# REDLED.net
KiCad netlist of a schematic drawn in Altium Designer
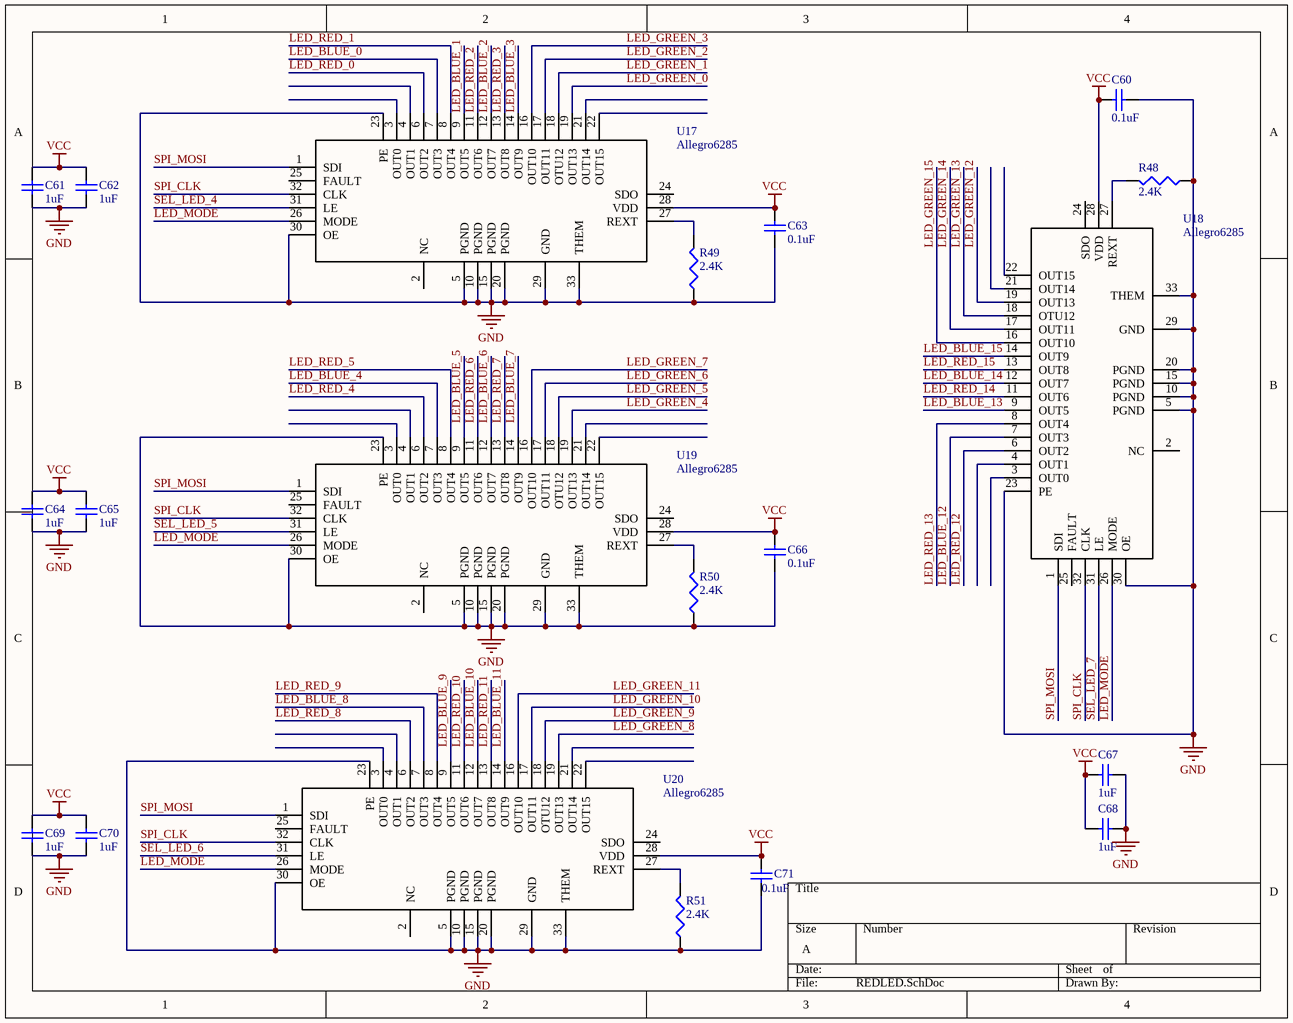
[diagram p0: REDLED.SchDoc]

(export (version "E")
  (design (tool "Eeschema 10.0.6"))
  (components
    (comp (ref "C60")
      (value "0.1uF")
      (footprint "CAPC1005L")
      (description "Capacitor (Semiconductor SIM Model)")
      (fields (field (name "Comment") "Cap Semi") (field (name "PUBLISHER") "Altium Limited"))
      (libsource (lib "Miscellaneous Devices") (part "Cap Semi"))
    )
    (comp (ref "C61")
      (value "1uF")
      (footprint "CAPC1608L")
      (description "Capacitor (Semiconductor SIM Model)")
      (fields (field (name "Comment") "Cap Semi") (field (name "PUBLISHER") "Altium Limited"))
      (libsource (lib "Miscellaneous Devices") (part "Cap Semi"))
    )
    (comp (ref "C62")
      (value "1uF")
      (footprint "CAPC1608L")
      (description "Capacitor (Semiconductor SIM Model)")
      (fields (field (name "Comment") "Cap Semi") (field (name "PUBLISHER") "Altium Limited"))
      (libsource (lib "Miscellaneous Devices") (part "Cap Semi"))
    )
    (comp (ref "C63")
      (value "0.1uF")
      (footprint "CAPC1005L")
      (description "Capacitor (Semiconductor SIM Model)")
      (fields (field (name "Comment") "Cap Semi") (field (name "PUBLISHER") "Altium Limited"))
      (libsource (lib "Miscellaneous Devices") (part "Cap Semi"))
    )
    (comp (ref "C64")
      (value "1uF")
      (footprint "CAPC1608L")
      (description "Capacitor (Semiconductor SIM Model)")
      (fields (field (name "Comment") "Cap Semi") (field (name "PUBLISHER") "Altium Limited"))
      (libsource (lib "Miscellaneous Devices") (part "Cap Semi"))
    )
    (comp (ref "C65")
      (value "1uF")
      (footprint "CAPC1608L")
      (description "Capacitor (Semiconductor SIM Model)")
      (fields (field (name "Comment") "Cap Semi") (field (name "PUBLISHER") "Altium Limited"))
      (libsource (lib "Miscellaneous Devices") (part "Cap Semi"))
    )
    (comp (ref "C66")
      (value "0.1uF")
      (footprint "CAPC1005L")
      (description "Capacitor (Semiconductor SIM Model)")
      (fields (field (name "Comment") "Cap Semi") (field (name "PUBLISHER") "Altium Limited"))
      (libsource (lib "Miscellaneous Devices") (part "Cap Semi"))
    )
    (comp (ref "C67")
      (value "1uF")
      (footprint "CAPC1608L")
      (description "Capacitor (Semiconductor SIM Model)")
      (fields (field (name "Comment") "Cap Semi") (field (name "PUBLISHER") "Altium Limited"))
      (libsource (lib "Miscellaneous Devices") (part "Cap Semi"))
    )
    (comp (ref "C68")
      (value "1uF")
      (footprint "CAPC1608L")
      (description "Capacitor (Semiconductor SIM Model)")
      (fields (field (name "Comment") "Cap Semi") (field (name "PUBLISHER") "Altium Limited"))
      (libsource (lib "Miscellaneous Devices") (part "Cap Semi"))
    )
    (comp (ref "C69")
      (value "1uF")
      (footprint "CAPC1608L")
      (description "Capacitor (Semiconductor SIM Model)")
      (fields (field (name "Comment") "Cap Semi") (field (name "PUBLISHER") "Altium Limited"))
      (libsource (lib "Miscellaneous Devices") (part "Cap Semi"))
    )
    (comp (ref "C70")
      (value "1uF")
      (footprint "CAPC1608L")
      (description "Capacitor (Semiconductor SIM Model)")
      (fields (field (name "Comment") "Cap Semi") (field (name "PUBLISHER") "Altium Limited"))
      (libsource (lib "Miscellaneous Devices") (part "Cap Semi"))
    )
    (comp (ref "C71")
      (value "0.1uF")
      (footprint "CAPC1005L")
      (description "Capacitor (Semiconductor SIM Model)")
      (fields (field (name "Comment") "Cap Semi") (field (name "PUBLISHER") "Altium Limited"))
      (libsource (lib "Miscellaneous Devices") (part "Cap Semi"))
    )
    (comp (ref "R48")
      (value "2.4K")
      (footprint "RESC1608L")
      (description "Resistor")
      (fields (field (name "Comment") "Res3") (field (name "PUBLISHER") "Altium Limited"))
      (libsource (lib "Miscellaneous Devices") (part "Res3"))
    )
    (comp (ref "R49")
      (value "2.4K")
      (footprint "RESC1608L")
      (description "Resistor")
      (fields (field (name "Comment") "Res3") (field (name "PUBLISHER") "Altium Limited"))
      (libsource (lib "Miscellaneous Devices") (part "Res3"))
    )
    (comp (ref "R50")
      (value "2.4K")
      (footprint "RESC1608L")
      (description "Resistor")
      (fields (field (name "Comment") "Res3") (field (name "PUBLISHER") "Altium Limited"))
      (libsource (lib "Miscellaneous Devices") (part "Res3"))
    )
    (comp (ref "R51")
      (value "2.4K")
      (footprint "RESC1608L")
      (description "Resistor")
      (fields (field (name "Comment") "Res3") (field (name "PUBLISHER") "Altium Limited"))
      (libsource (lib "Miscellaneous Devices") (part "Res3"))
    )
    (comp (ref "U17")
      (value "Allegro6285")
      (footprint "QFN-32")
      (libsource (lib "mrone") (part "Allegro6285"))
    )
    (comp (ref "U18")
      (value "Allegro6285")
      (footprint "QFN-32")
      (libsource (lib "mrone") (part "Allegro6285"))
    )
    (comp (ref "U19")
      (value "Allegro6285")
      (footprint "QFN-32")
      (libsource (lib "mrone") (part "Allegro6285"))
    )
    (comp (ref "U20")
      (value "Allegro6285")
      (footprint "QFN-32")
      (libsource (lib "mrone") (part "Allegro6285"))
    )
  )
  (nets
    (net (code "1") (name "/LED_BLUE_0") (class "Default")
      (node (ref "U17") (pin "7") (pinfunction "OUT3_7") (pintype "passive"))
    )
    (net (code "2") (name "/LED_BLUE_1") (class "Default")
      (node (ref "U17") (pin "9") (pinfunction "OUT5_9") (pintype "passive"))
    )
    (net (code "3") (name "/LED_BLUE_2") (class "Default")
      (node (ref "U17") (pin "12") (pinfunction "OUT7_12") (pintype "passive"))
    )
    (net (code "4") (name "/LED_BLUE_3") (class "Default")
      (node (ref "U17") (pin "14") (pinfunction "OUT9_14") (pintype "passive"))
    )
    (net (code "5") (name "/LED_BLUE_4") (class "Default")
      (node (ref "U19") (pin "7") (pinfunction "OUT3_7") (pintype "passive"))
    )
    (net (code "6") (name "/LED_BLUE_5") (class "Default")
      (node (ref "U19") (pin "9") (pinfunction "OUT5_9") (pintype "passive"))
    )
    (net (code "7") (name "/LED_BLUE_6") (class "Default")
      (node (ref "U19") (pin "12") (pinfunction "OUT7_12") (pintype "passive"))
    )
    (net (code "8") (name "/LED_BLUE_7") (class "Default")
      (node (ref "U19") (pin "14") (pinfunction "OUT9_14") (pintype "passive"))
    )
    (net (code "9") (name "/LED_BLUE_8") (class "Default")
      (node (ref "U20") (pin "7") (pinfunction "OUT3_7") (pintype "passive"))
    )
    (net (code "10") (name "/LED_BLUE_9") (class "Default")
      (node (ref "U20") (pin "9") (pinfunction "OUT5_9") (pintype "passive"))
    )
    (net (code "11") (name "/LED_BLUE_10") (class "Default")
      (node (ref "U20") (pin "12") (pinfunction "OUT7_12") (pintype "passive"))
    )
    (net (code "12") (name "/LED_BLUE_11") (class "Default")
      (node (ref "U20") (pin "14") (pinfunction "OUT9_14") (pintype "passive"))
    )
    (net (code "13") (name "/LED_BLUE_12") (class "Default")
      (node (ref "U18") (pin "7") (pinfunction "OUT3_7") (pintype "passive"))
    )
    (net (code "14") (name "/LED_BLUE_13") (class "Default")
      (node (ref "U18") (pin "9") (pinfunction "OUT5_9") (pintype "passive"))
    )
    (net (code "15") (name "/LED_BLUE_14") (class "Default")
      (node (ref "U18") (pin "12") (pinfunction "OUT7_12") (pintype "passive"))
    )
    (net (code "16") (name "/LED_BLUE_15") (class "Default")
      (node (ref "U18") (pin "14") (pinfunction "OUT9_14") (pintype "passive"))
    )
    (net (code "17") (name "/LED_GREEN_0") (class "Default")
      (node (ref "U17") (pin "19") (pinfunction "OUT13_19") (pintype "passive"))
    )
    (net (code "18") (name "/LED_GREEN_1") (class "Default")
      (node (ref "U17") (pin "18") (pinfunction "OTU12_18") (pintype "passive"))
    )
    (net (code "19") (name "/LED_GREEN_2") (class "Default")
      (node (ref "U17") (pin "17") (pinfunction "OUT11_17") (pintype "passive"))
    )
    (net (code "20") (name "/LED_GREEN_3") (class "Default")
      (node (ref "U17") (pin "16") (pinfunction "OUT10_16") (pintype "passive"))
    )
    (net (code "21") (name "/LED_GREEN_4") (class "Default")
      (node (ref "U19") (pin "19") (pinfunction "OUT13_19") (pintype "passive"))
    )
    (net (code "22") (name "/LED_GREEN_5") (class "Default")
      (node (ref "U19") (pin "18") (pinfunction "OTU12_18") (pintype "passive"))
    )
    (net (code "23") (name "/LED_GREEN_6") (class "Default")
      (node (ref "U19") (pin "17") (pinfunction "OUT11_17") (pintype "passive"))
    )
    (net (code "24") (name "/LED_GREEN_7") (class "Default")
      (node (ref "U19") (pin "16") (pinfunction "OUT10_16") (pintype "passive"))
    )
    (net (code "25") (name "/LED_GREEN_8") (class "Default")
      (node (ref "U20") (pin "19") (pinfunction "OUT13_19") (pintype "passive"))
    )
    (net (code "26") (name "/LED_GREEN_9") (class "Default")
      (node (ref "U20") (pin "18") (pinfunction "OTU12_18") (pintype "passive"))
    )
    (net (code "27") (name "/LED_GREEN_10") (class "Default")
      (node (ref "U20") (pin "17") (pinfunction "OUT11_17") (pintype "passive"))
    )
    (net (code "28") (name "/LED_GREEN_11") (class "Default")
      (node (ref "U20") (pin "16") (pinfunction "OUT10_16") (pintype "passive"))
    )
    (net (code "29") (name "/LED_GREEN_12") (class "Default")
      (node (ref "U18") (pin "19") (pinfunction "OUT13_19") (pintype "passive"))
    )
    (net (code "30") (name "/LED_GREEN_13") (class "Default")
      (node (ref "U18") (pin "18") (pinfunction "OTU12_18") (pintype "passive"))
    )
    (net (code "31") (name "/LED_GREEN_14") (class "Default")
      (node (ref "U18") (pin "17") (pinfunction "OUT11_17") (pintype "passive"))
    )
    (net (code "32") (name "/LED_GREEN_15") (class "Default")
      (node (ref "U18") (pin "16") (pinfunction "OUT10_16") (pintype "passive"))
    )
    (net (code "33") (name "/LED_MODE") (class "Default")
      (node (ref "U17") (pin "26") (pinfunction "MODE_26") (pintype "passive"))
      (node (ref "U18") (pin "26") (pinfunction "MODE_26") (pintype "passive"))
      (node (ref "U19") (pin "26") (pinfunction "MODE_26") (pintype "passive"))
      (node (ref "U20") (pin "26") (pinfunction "MODE_26") (pintype "passive"))
    )
    (net (code "34") (name "/LED_RED_0") (class "Default")
      (node (ref "U17") (pin "6") (pinfunction "OUT2_6") (pintype "passive"))
    )
    (net (code "35") (name "/LED_RED_1") (class "Default")
      (node (ref "U17") (pin "8") (pinfunction "OUT4_8") (pintype "passive"))
    )
    (net (code "36") (name "/LED_RED_2") (class "Default")
      (node (ref "U17") (pin "11") (pinfunction "OUT6_11") (pintype "passive"))
    )
    (net (code "37") (name "/LED_RED_3") (class "Default")
      (node (ref "U17") (pin "13") (pinfunction "OUT8_13") (pintype "passive"))
    )
    (net (code "38") (name "/LED_RED_4") (class "Default")
      (node (ref "U19") (pin "6") (pinfunction "OUT2_6") (pintype "passive"))
    )
    (net (code "39") (name "/LED_RED_5") (class "Default")
      (node (ref "U19") (pin "8") (pinfunction "OUT4_8") (pintype "passive"))
    )
    (net (code "40") (name "/LED_RED_6") (class "Default")
      (node (ref "U19") (pin "11") (pinfunction "OUT6_11") (pintype "passive"))
    )
    (net (code "41") (name "/LED_RED_7") (class "Default")
      (node (ref "U19") (pin "13") (pinfunction "OUT8_13") (pintype "passive"))
    )
    (net (code "42") (name "/LED_RED_8") (class "Default")
      (node (ref "U20") (pin "6") (pinfunction "OUT2_6") (pintype "passive"))
    )
    (net (code "43") (name "/LED_RED_9") (class "Default")
      (node (ref "U20") (pin "8") (pinfunction "OUT4_8") (pintype "passive"))
    )
    (net (code "44") (name "/LED_RED_10") (class "Default")
      (node (ref "U20") (pin "11") (pinfunction "OUT6_11") (pintype "passive"))
    )
    (net (code "45") (name "/LED_RED_11") (class "Default")
      (node (ref "U20") (pin "13") (pinfunction "OUT8_13") (pintype "passive"))
    )
    (net (code "46") (name "/LED_RED_12") (class "Default")
      (node (ref "U18") (pin "6") (pinfunction "OUT2_6") (pintype "passive"))
    )
    (net (code "47") (name "/LED_RED_13") (class "Default")
      (node (ref "U18") (pin "8") (pinfunction "OUT4_8") (pintype "passive"))
    )
    (net (code "48") (name "/LED_RED_14") (class "Default")
      (node (ref "U18") (pin "11") (pinfunction "OUT6_11") (pintype "passive"))
    )
    (net (code "49") (name "/LED_RED_15") (class "Default")
      (node (ref "U18") (pin "13") (pinfunction "OUT8_13") (pintype "passive"))
    )
    (net (code "50") (name "/SEL_LED_4") (class "Default")
      (node (ref "U17") (pin "31") (pinfunction "LE_31") (pintype "passive"))
    )
    (net (code "51") (name "/SEL_LED_5") (class "Default")
      (node (ref "U19") (pin "31") (pinfunction "LE_31") (pintype "passive"))
    )
    (net (code "52") (name "/SEL_LED_6") (class "Default")
      (node (ref "U20") (pin "31") (pinfunction "LE_31") (pintype "passive"))
    )
    (net (code "53") (name "/SEL_LED_7") (class "Default")
      (node (ref "U18") (pin "31") (pinfunction "LE_31") (pintype "passive"))
    )
    (net (code "54") (name "/SPI_CLK") (class "Default")
      (node (ref "U17") (pin "32") (pinfunction "CLK_32") (pintype "passive"))
      (node (ref "U18") (pin "32") (pinfunction "CLK_32") (pintype "passive"))
      (node (ref "U19") (pin "32") (pinfunction "CLK_32") (pintype "passive"))
      (node (ref "U20") (pin "32") (pinfunction "CLK_32") (pintype "passive"))
    )
    (net (code "55") (name "/SPI_MOSI") (class "Default")
      (node (ref "U17") (pin "1") (pinfunction "SDI_1") (pintype "passive"))
      (node (ref "U18") (pin "1") (pinfunction "SDI_1") (pintype "passive"))
      (node (ref "U19") (pin "1") (pinfunction "SDI_1") (pintype "passive"))
      (node (ref "U20") (pin "1") (pinfunction "SDI_1") (pintype "passive"))
    )
    (net (code "56") (name "GND") (class "Default")
      (node (ref "C60") (pin "1") (pinfunction "1_1") (pintype "passive"))
      (node (ref "C61") (pin "1") (pinfunction "1_1") (pintype "passive"))
      (node (ref "C62") (pin "1") (pinfunction "1_1") (pintype "passive"))
      (node (ref "C63") (pin "1") (pinfunction "1_1") (pintype "passive"))
      (node (ref "C64") (pin "1") (pinfunction "1_1") (pintype "passive"))
      (node (ref "C65") (pin "1") (pinfunction "1_1") (pintype "passive"))
      (node (ref "C66") (pin "1") (pinfunction "1_1") (pintype "passive"))
      (node (ref "C67") (pin "1") (pinfunction "1_1") (pintype "passive"))
      (node (ref "C68") (pin "1") (pinfunction "1_1") (pintype "passive"))
      (node (ref "C69") (pin "1") (pinfunction "1_1") (pintype "passive"))
      (node (ref "C70") (pin "1") (pinfunction "1_1") (pintype "passive"))
      (node (ref "C71") (pin "1") (pinfunction "1_1") (pintype "passive"))
      (node (ref "R48") (pin "1") (pinfunction "1_1") (pintype "passive"))
      (node (ref "R49") (pin "1") (pinfunction "1_1") (pintype "passive"))
      (node (ref "R50") (pin "1") (pinfunction "1_1") (pintype "passive"))
      (node (ref "R51") (pin "1") (pinfunction "1_1") (pintype "passive"))
      (node (ref "U17") (pin "10") (pinfunction "PGND_10") (pintype "passive"))
      (node (ref "U17") (pin "15") (pinfunction "PGND_15") (pintype "passive"))
      (node (ref "U17") (pin "20") (pinfunction "PGND_20") (pintype "passive"))
      (node (ref "U17") (pin "23") (pinfunction "PE_23") (pintype "passive"))
      (node (ref "U17") (pin "29") (pinfunction "GND_29") (pintype "passive"))
      (node (ref "U17") (pin "30") (pinfunction "OE_30") (pintype "passive"))
      (node (ref "U17") (pin "33") (pinfunction "THEM_33") (pintype "passive"))
      (node (ref "U17") (pin "5") (pinfunction "PGND_5") (pintype "passive"))
      (node (ref "U18") (pin "10") (pinfunction "PGND_10") (pintype "passive"))
      (node (ref "U18") (pin "15") (pinfunction "PGND_15") (pintype "passive"))
      (node (ref "U18") (pin "20") (pinfunction "PGND_20") (pintype "passive"))
      (node (ref "U18") (pin "23") (pinfunction "PE_23") (pintype "passive"))
      (node (ref "U18") (pin "29") (pinfunction "GND_29") (pintype "passive"))
      (node (ref "U18") (pin "30") (pinfunction "OE_30") (pintype "passive"))
      (node (ref "U18") (pin "33") (pinfunction "THEM_33") (pintype "passive"))
      (node (ref "U18") (pin "5") (pinfunction "PGND_5") (pintype "passive"))
      (node (ref "U19") (pin "10") (pinfunction "PGND_10") (pintype "passive"))
      (node (ref "U19") (pin "15") (pinfunction "PGND_15") (pintype "passive"))
      (node (ref "U19") (pin "20") (pinfunction "PGND_20") (pintype "passive"))
      (node (ref "U19") (pin "23") (pinfunction "PE_23") (pintype "passive"))
      (node (ref "U19") (pin "29") (pinfunction "GND_29") (pintype "passive"))
      (node (ref "U19") (pin "30") (pinfunction "OE_30") (pintype "passive"))
      (node (ref "U19") (pin "33") (pinfunction "THEM_33") (pintype "passive"))
      (node (ref "U19") (pin "5") (pinfunction "PGND_5") (pintype "passive"))
      (node (ref "U20") (pin "10") (pinfunction "PGND_10") (pintype "passive"))
      (node (ref "U20") (pin "15") (pinfunction "PGND_15") (pintype "passive"))
      (node (ref "U20") (pin "20") (pinfunction "PGND_20") (pintype "passive"))
      (node (ref "U20") (pin "23") (pinfunction "PE_23") (pintype "passive"))
      (node (ref "U20") (pin "29") (pinfunction "GND_29") (pintype "passive"))
      (node (ref "U20") (pin "30") (pinfunction "OE_30") (pintype "passive"))
      (node (ref "U20") (pin "33") (pinfunction "THEM_33") (pintype "passive"))
      (node (ref "U20") (pin "5") (pinfunction "PGND_5") (pintype "passive"))
    )
    (net (code "57") (name "Net-(U17-REXT)") (class "Default")
      (node (ref "R49") (pin "2") (pinfunction "2_2") (pintype "passive"))
      (node (ref "U17") (pin "27") (pinfunction "REXT_27") (pintype "passive"))
    )
    (net (code "58") (name "Net-(U18-REXT)") (class "Default")
      (node (ref "R48") (pin "2") (pinfunction "2_2") (pintype "passive"))
      (node (ref "U18") (pin "27") (pinfunction "REXT_27") (pintype "passive"))
    )
    (net (code "59") (name "Net-(U19-REXT)") (class "Default")
      (node (ref "R50") (pin "2") (pinfunction "2_2") (pintype "passive"))
      (node (ref "U19") (pin "27") (pinfunction "REXT_27") (pintype "passive"))
    )
    (net (code "60") (name "Net-(U20-REXT)") (class "Default")
      (node (ref "R51") (pin "2") (pinfunction "2_2") (pintype "passive"))
      (node (ref "U20") (pin "27") (pinfunction "REXT_27") (pintype "passive"))
    )
    (net (code "61") (name "VCC") (class "Default")
      (node (ref "C60") (pin "2") (pinfunction "2_2") (pintype "passive"))
      (node (ref "C61") (pin "2") (pinfunction "2_2") (pintype "passive"))
      (node (ref "C62") (pin "2") (pinfunction "2_2") (pintype "passive"))
      (node (ref "C63") (pin "2") (pinfunction "2_2") (pintype "passive"))
      (node (ref "C64") (pin "2") (pinfunction "2_2") (pintype "passive"))
      (node (ref "C65") (pin "2") (pinfunction "2_2") (pintype "passive"))
      (node (ref "C66") (pin "2") (pinfunction "2_2") (pintype "passive"))
      (node (ref "C67") (pin "2") (pinfunction "2_2") (pintype "passive"))
      (node (ref "C68") (pin "2") (pinfunction "2_2") (pintype "passive"))
      (node (ref "C69") (pin "2") (pinfunction "2_2") (pintype "passive"))
      (node (ref "C70") (pin "2") (pinfunction "2_2") (pintype "passive"))
      (node (ref "C71") (pin "2") (pinfunction "2_2") (pintype "passive"))
      (node (ref "U17") (pin "28") (pinfunction "VDD_28") (pintype "passive"))
      (node (ref "U18") (pin "28") (pinfunction "VDD_28") (pintype "passive"))
      (node (ref "U19") (pin "28") (pinfunction "VDD_28") (pintype "passive"))
      (node (ref "U20") (pin "28") (pinfunction "VDD_28") (pintype "passive"))
    )
    (net (code "62") (name "unconnected-(U17-FAULT-Pad25)") (class "Default")
      (node (ref "U17") (pin "25") (pinfunction "FAULT_25") (pintype "passive"))
    )
    (net (code "63") (name "unconnected-(U17-NC-Pad2)") (class "Default")
      (node (ref "U17") (pin "2") (pinfunction "NC_2") (pintype "passive"))
    )
    (net (code "64") (name "unconnected-(U17-OUT0-Pad3)") (class "Default")
      (node (ref "U17") (pin "3") (pinfunction "OUT0_3") (pintype "passive"))
    )
    (net (code "65") (name "unconnected-(U17-OUT1-Pad4)") (class "Default")
      (node (ref "U17") (pin "4") (pinfunction "OUT1_4") (pintype "passive"))
    )
    (net (code "66") (name "unconnected-(U17-OUT14-Pad21)") (class "Default")
      (node (ref "U17") (pin "21") (pinfunction "OUT14_21") (pintype "passive"))
    )
    (net (code "67") (name "unconnected-(U17-OUT15-Pad22)") (class "Default")
      (node (ref "U17") (pin "22") (pinfunction "OUT15_22") (pintype "passive"))
    )
    (net (code "68") (name "unconnected-(U17-SDO-Pad24)") (class "Default")
      (node (ref "U17") (pin "24") (pinfunction "SDO_24") (pintype "passive"))
    )
    (net (code "69") (name "unconnected-(U18-FAULT-Pad25)") (class "Default")
      (node (ref "U18") (pin "25") (pinfunction "FAULT_25") (pintype "passive"))
    )
    (net (code "70") (name "unconnected-(U18-NC-Pad2)") (class "Default")
      (node (ref "U18") (pin "2") (pinfunction "NC_2") (pintype "passive"))
    )
    (net (code "71") (name "unconnected-(U18-OUT0-Pad3)") (class "Default")
      (node (ref "U18") (pin "3") (pinfunction "OUT0_3") (pintype "passive"))
    )
    (net (code "72") (name "unconnected-(U18-OUT1-Pad4)") (class "Default")
      (node (ref "U18") (pin "4") (pinfunction "OUT1_4") (pintype "passive"))
    )
    (net (code "73") (name "unconnected-(U18-OUT14-Pad21)") (class "Default")
      (node (ref "U18") (pin "21") (pinfunction "OUT14_21") (pintype "passive"))
    )
    (net (code "74") (name "unconnected-(U18-OUT15-Pad22)") (class "Default")
      (node (ref "U18") (pin "22") (pinfunction "OUT15_22") (pintype "passive"))
    )
    (net (code "75") (name "unconnected-(U18-SDO-Pad24)") (class "Default")
      (node (ref "U18") (pin "24") (pinfunction "SDO_24") (pintype "passive"))
    )
    (net (code "76") (name "unconnected-(U19-FAULT-Pad25)") (class "Default")
      (node (ref "U19") (pin "25") (pinfunction "FAULT_25") (pintype "passive"))
    )
    (net (code "77") (name "unconnected-(U19-NC-Pad2)") (class "Default")
      (node (ref "U19") (pin "2") (pinfunction "NC_2") (pintype "passive"))
    )
    (net (code "78") (name "unconnected-(U19-OUT0-Pad3)") (class "Default")
      (node (ref "U19") (pin "3") (pinfunction "OUT0_3") (pintype "passive"))
    )
    (net (code "79") (name "unconnected-(U19-OUT1-Pad4)") (class "Default")
      (node (ref "U19") (pin "4") (pinfunction "OUT1_4") (pintype "passive"))
    )
    (net (code "80") (name "unconnected-(U19-OUT14-Pad21)") (class "Default")
      (node (ref "U19") (pin "21") (pinfunction "OUT14_21") (pintype "passive"))
    )
    (net (code "81") (name "unconnected-(U19-OUT15-Pad22)") (class "Default")
      (node (ref "U19") (pin "22") (pinfunction "OUT15_22") (pintype "passive"))
    )
    (net (code "82") (name "unconnected-(U19-SDO-Pad24)") (class "Default")
      (node (ref "U19") (pin "24") (pinfunction "SDO_24") (pintype "passive"))
    )
    (net (code "83") (name "unconnected-(U20-FAULT-Pad25)") (class "Default")
      (node (ref "U20") (pin "25") (pinfunction "FAULT_25") (pintype "passive"))
    )
    (net (code "84") (name "unconnected-(U20-NC-Pad2)") (class "Default")
      (node (ref "U20") (pin "2") (pinfunction "NC_2") (pintype "passive"))
    )
    (net (code "85") (name "unconnected-(U20-OUT0-Pad3)") (class "Default")
      (node (ref "U20") (pin "3") (pinfunction "OUT0_3") (pintype "passive"))
    )
    (net (code "86") (name "unconnected-(U20-OUT1-Pad4)") (class "Default")
      (node (ref "U20") (pin "4") (pinfunction "OUT1_4") (pintype "passive"))
    )
    (net (code "87") (name "unconnected-(U20-OUT14-Pad21)") (class "Default")
      (node (ref "U20") (pin "21") (pinfunction "OUT14_21") (pintype "passive"))
    )
    (net (code "88") (name "unconnected-(U20-OUT15-Pad22)") (class "Default")
      (node (ref "U20") (pin "22") (pinfunction "OUT15_22") (pintype "passive"))
    )
    (net (code "89") (name "unconnected-(U20-SDO-Pad24)") (class "Default")
      (node (ref "U20") (pin "24") (pinfunction "SDO_24") (pintype "passive"))
    )
  )
)
